# Button_Led_Buzzer_SMD_0603.net
KiCad netlist of a schematic drawn in EAGLE
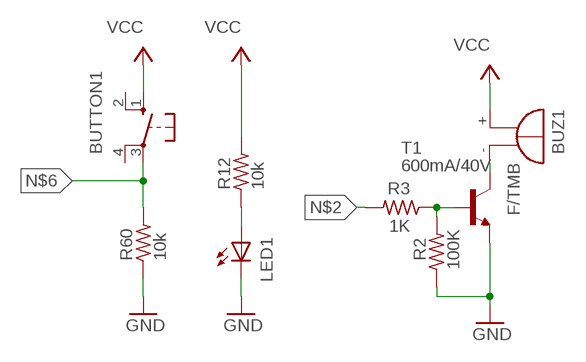
[diagram p0: schematic, sheet 1]

(export (version "E")
  (design (tool "Eeschema 10.0.6"))
  (components
    (comp (ref "BUTTON1")
      (value "10-XX")
      (footprint "eagle-import:B3F-10XX")
      (fields (field (name "MPN") "B3F-1000"))
      (libsource (lib "eagle-import") (part "10-XX"))
    )
    (comp (ref "BUZ1")
      (value "F/TMB")
      (footprint "eagle-import:F_TMB")
      (fields (field (name "SPICEPREFIX") "B"))
      (libsource (lib "eagle-import") (part "F/TMB"))
    )
    (comp (ref "LED1")
      (value "LEDCHIPLED_0603")
      (footprint "eagle-import:CHIPLED_0603")
      (libsource (lib "eagle-import") (part "LEDCHIPLED_0603"))
    )
    (comp (ref "R2")
      (value "100K")
      (footprint "eagle-import:R0603")
      (libsource (lib "eagle-import") (part "R-US_R0603"))
    )
    (comp (ref "R3")
      (value "1K")
      (footprint "eagle-import:R0603")
      (libsource (lib "eagle-import") (part "R-US_R0603"))
    )
    (comp (ref "R12")
      (value "10k")
      (footprint "eagle-import:R0603")
      (libsource (lib "eagle-import") (part "R-US_R0603"))
    )
    (comp (ref "R60")
      (value "10k")
      (footprint "eagle-import:R0603")
      (libsource (lib "eagle-import") (part "R-US_R0603"))
    )
    (comp (ref "T1")
      (value "600mA/40V")
      (footprint "eagle-import:SOT23-3")
      (libsource (lib "eagle-import") (part "TRANS_NPN-MMBT2222AL"))
    )
  )
  (nets
    (net (code "1") (name "GND") (class "Default")
      (node (ref "LED1") (pin "C") (pinfunction "C_C") (pintype "passive"))
      (node (ref "R2") (pin "1") (pinfunction "1_1") (pintype "passive"))
      (node (ref "R60") (pin "1") (pinfunction "1_1") (pintype "passive"))
      (node (ref "T1") (pin "2") (pinfunction "E_2") (pintype "passive"))
    )
    (net (code "2") (name "N$2") (class "Default")
      (node (ref "R3") (pin "2") (pinfunction "2_2") (pintype "passive"))
    )
    (net (code "3") (name "N$6") (class "Default")
      (node (ref "BUTTON1") (pin "3") (pinfunction "P_3") (pintype "passive"))
      (node (ref "R60") (pin "2") (pinfunction "2_2") (pintype "passive"))
    )
    (net (code "4") (name "Net-(LED1-PadA)") (class "Default")
      (node (ref "LED1") (pin "A") (pinfunction "A_A") (pintype "passive"))
      (node (ref "R12") (pin "1") (pinfunction "1_1") (pintype "passive"))
    )
    (net (code "5") (name "Net-(T1-B)") (class "Default")
      (node (ref "R2") (pin "2") (pinfunction "2_2") (pintype "passive"))
      (node (ref "R3") (pin "1") (pinfunction "1_1") (pintype "passive"))
      (node (ref "T1") (pin "1") (pinfunction "B_1") (pintype "passive"))
    )
    (net (code "6") (name "Net-(T1-C)") (class "Default")
      (node (ref "BUZ1") (pin "-") (pinfunction "-_-") (pintype "passive"))
      (node (ref "T1") (pin "3") (pinfunction "C_3") (pintype "passive"))
    )
    (net (code "7") (name "VCC") (class "Default")
      (node (ref "BUTTON1") (pin "1") (pinfunction "S_1") (pintype "passive"))
      (node (ref "BUZ1") (pin "+") (pinfunction "+_+") (pintype "passive"))
      (node (ref "R12") (pin "2") (pinfunction "2_2") (pintype "passive"))
    )
    (net (code "8") (name "unconnected-(BUTTON1-P1-Pad4)") (class "Default")
      (node (ref "BUTTON1") (pin "4") (pinfunction "P1_4") (pintype "passive"))
    )
    (net (code "9") (name "unconnected-(BUTTON1-S1-Pad2)") (class "Default")
      (node (ref "BUTTON1") (pin "2") (pinfunction "S1_2") (pintype "passive"))
    )
  )
)
